# HPF_1_0.net
KiCad netlist of a schematic drawn in EAGLE
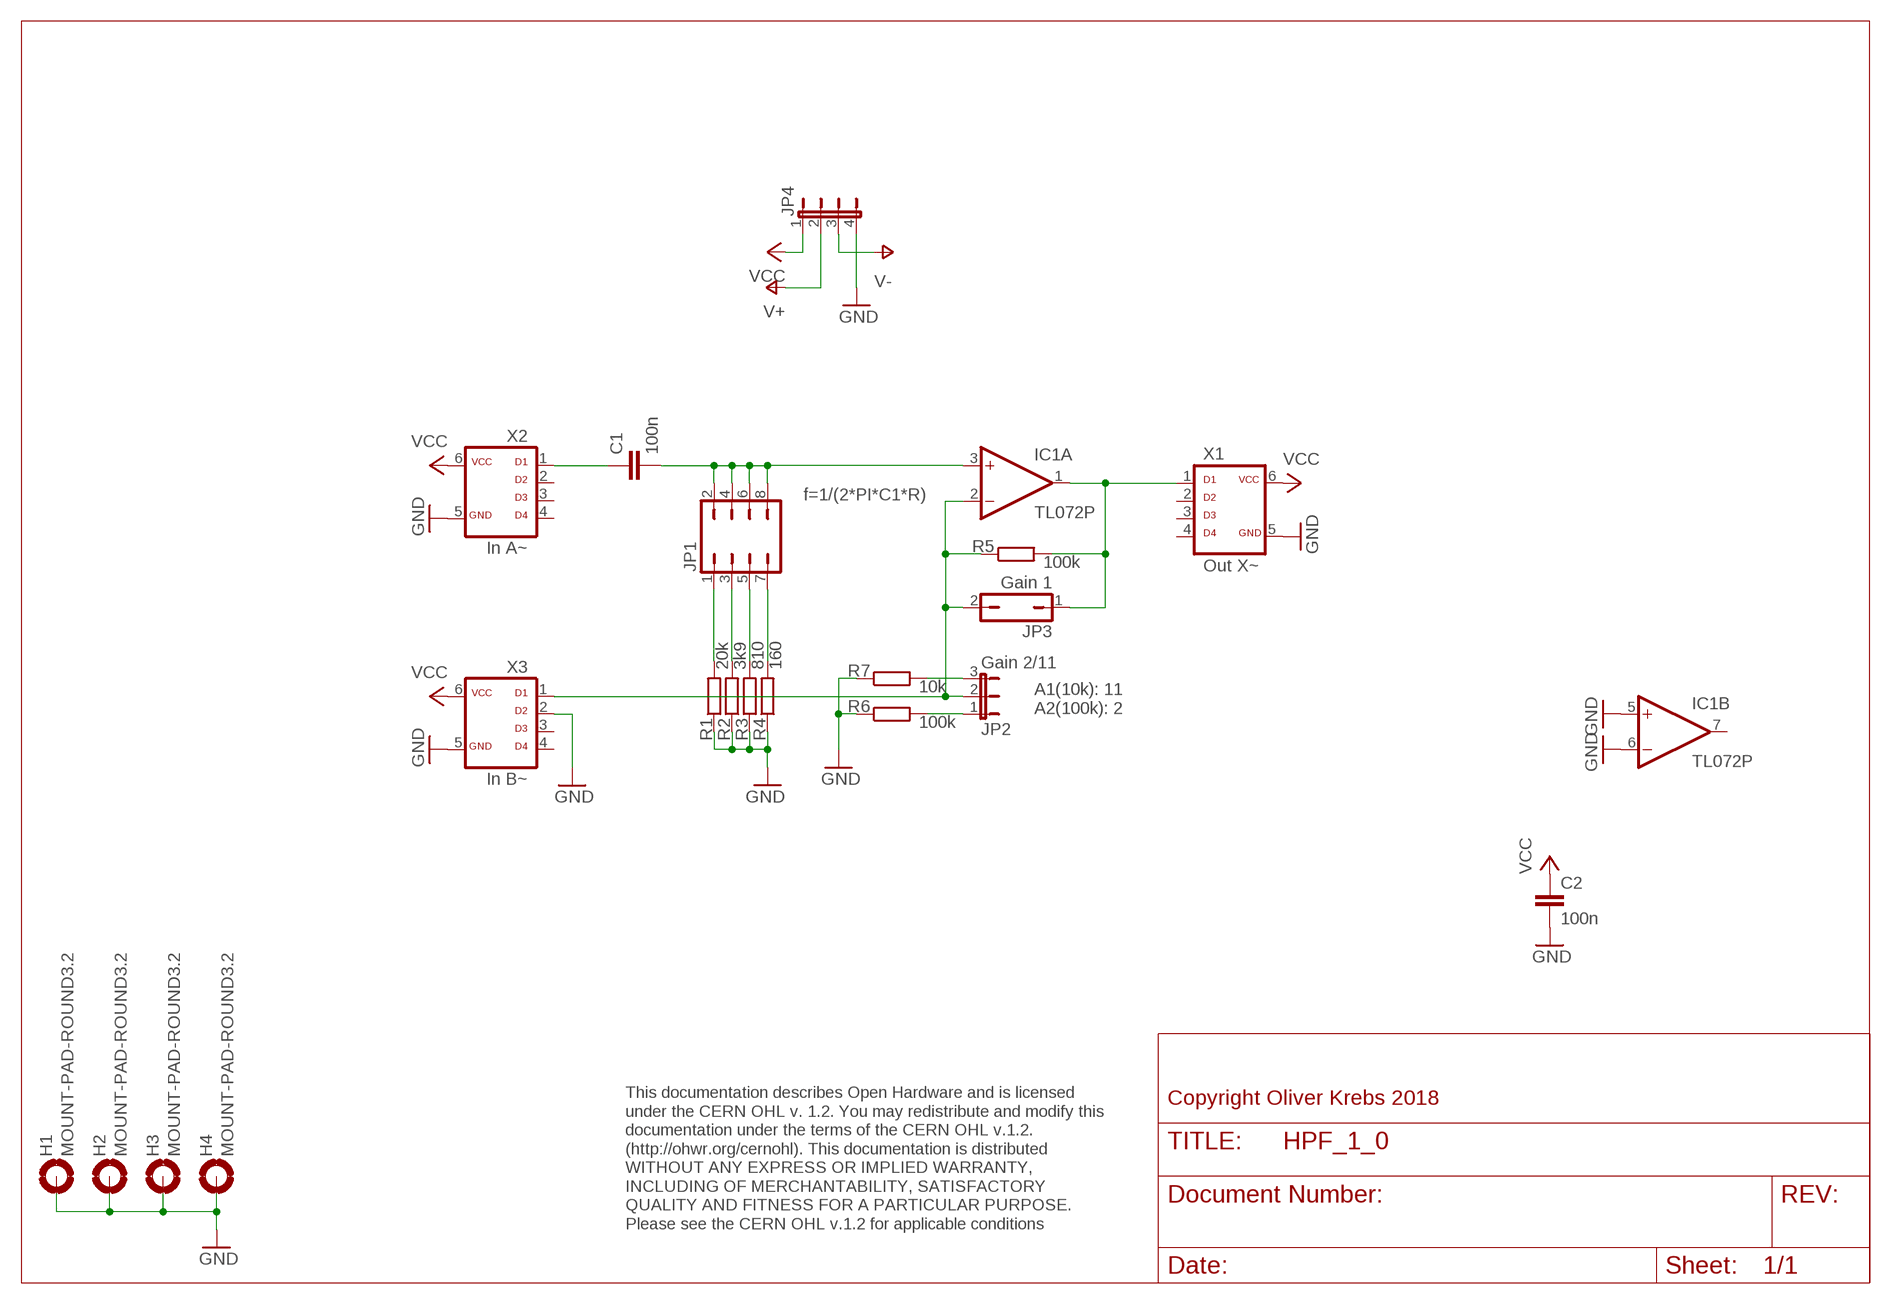
[diagram p0: schematic, sheet 1]

(export (version "E")
  (design (tool "Eeschema 10.0.6"))
  (components
    (comp (ref "C1")
      (value "100n")
      (footprint "eagle-import:C050-025X075")
      (libsource (lib "eagle-import") (part "C-EU050-025X075"))
    )
    (comp (ref "C2")
      (value "100n")
      (footprint "eagle-import:C050-025X075")
      (libsource (lib "eagle-import") (part "C-EU050-025X075"))
    )
    (comp (ref "H1")
      (value "MOUNT-PAD-ROUND3.2")
      (footprint "eagle-import:3,2-PAD")
      (libsource (lib "eagle-import") (part "MOUNT-PAD-ROUND3.2"))
    )
    (comp (ref "H2")
      (value "MOUNT-PAD-ROUND3.2")
      (footprint "eagle-import:3,2-PAD")
      (libsource (lib "eagle-import") (part "MOUNT-PAD-ROUND3.2"))
    )
    (comp (ref "H3")
      (value "MOUNT-PAD-ROUND3.2")
      (footprint "eagle-import:3,2-PAD")
      (libsource (lib "eagle-import") (part "MOUNT-PAD-ROUND3.2"))
    )
    (comp (ref "H4")
      (value "MOUNT-PAD-ROUND3.2")
      (footprint "eagle-import:3,2-PAD")
      (libsource (lib "eagle-import") (part "MOUNT-PAD-ROUND3.2"))
    )
    (comp (ref "IC1")
      (value "TL072P")
      (footprint "eagle-import:DIL08")
      (libsource (lib "eagle-import") (part "TL072P"))
    )
    (comp (ref "JP1")
      (value "JP4Q")
      (footprint "eagle-import:JP4Q")
      (libsource (lib "eagle-import") (part "JP4Q"))
    )
    (comp (ref "JP2")
      (value "Gain 2/11")
      (footprint "eagle-import:JP2-U")
      (libsource (lib "eagle-import") (part "JP2EJP2-U"))
    )
    (comp (ref "JP3")
      (value "Gain 1")
      (footprint "eagle-import:JP1")
      (libsource (lib "eagle-import") (part "JP1Q"))
    )
    (comp (ref "JP4")
      (value "JP4E")
      (footprint "eagle-import:JP4")
      (libsource (lib "eagle-import") (part "JP4E"))
    )
    (comp (ref "R1")
      (value "20k")
      (footprint "eagle-import:0207_10")
      (libsource (lib "eagle-import") (part "R-EU_0207/10"))
    )
    (comp (ref "R2")
      (value "3k9")
      (footprint "eagle-import:0207_10")
      (libsource (lib "eagle-import") (part "R-EU_0207/10"))
    )
    (comp (ref "R3")
      (value "810")
      (footprint "eagle-import:0207_10")
      (libsource (lib "eagle-import") (part "R-EU_0207/10"))
    )
    (comp (ref "R4")
      (value "160")
      (footprint "eagle-import:0207_10")
      (libsource (lib "eagle-import") (part "R-EU_0207/10"))
    )
    (comp (ref "R5")
      (value "100k")
      (footprint "eagle-import:0207_10")
      (libsource (lib "eagle-import") (part "R-EU_0207/10"))
    )
    (comp (ref "R6")
      (value "100k")
      (footprint "eagle-import:0207_10")
      (libsource (lib "eagle-import") (part "R-EU_0207/10"))
    )
    (comp (ref "R7")
      (value "10k")
      (footprint "eagle-import:0207_10")
      (libsource (lib "eagle-import") (part "R-EU_0207/10"))
    )
    (comp (ref "X1")
      (value "Out X~")
      (footprint "eagle-import:ML-6")
      (libsource (lib "eagle-import") (part "ML6D"))
    )
    (comp (ref "X2")
      (value "In A~")
      (footprint "eagle-import:ML-6")
      (libsource (lib "eagle-import") (part "ML6D"))
    )
    (comp (ref "X3")
      (value "In B~")
      (footprint "eagle-import:ML-6")
      (libsource (lib "eagle-import") (part "ML6D"))
    )
  )
  (nets
    (net (code "1") (name "GND") (class "Default")
      (node (ref "C2") (pin "2") (pinfunction "2_2") (pintype "passive"))
      (node (ref "H1") (pin "B3,2") (pinfunction "MOUNT_B3,2") (pintype "passive"))
      (node (ref "H2") (pin "B3,2") (pinfunction "MOUNT_B3,2") (pintype "passive"))
      (node (ref "H3") (pin "B3,2") (pinfunction "MOUNT_B3,2") (pintype "passive"))
      (node (ref "H4") (pin "B3,2") (pinfunction "MOUNT_B3,2") (pintype "passive"))
      (node (ref "IC1") (pin "5") (pinfunction "+IN_5") (pintype "input"))
      (node (ref "IC1") (pin "6") (pinfunction "-IN_6") (pintype "input"))
      (node (ref "JP4") (pin "4") (pinfunction "4_4") (pintype "passive"))
      (node (ref "R1") (pin "1") (pinfunction "1_1") (pintype "passive"))
      (node (ref "R2") (pin "1") (pinfunction "1_1") (pintype "passive"))
      (node (ref "R3") (pin "1") (pinfunction "1_1") (pintype "passive"))
      (node (ref "R4") (pin "1") (pinfunction "1_1") (pintype "passive"))
      (node (ref "R6") (pin "1") (pinfunction "1_1") (pintype "passive"))
      (node (ref "R7") (pin "1") (pinfunction "1_1") (pintype "passive"))
      (node (ref "X1") (pin "5") (pinfunction "5_5") (pintype "passive"))
      (node (ref "X2") (pin "5") (pinfunction "5_5") (pintype "passive"))
      (node (ref "X3") (pin "2") (pinfunction "2_2") (pintype "passive"))
      (node (ref "X3") (pin "5") (pinfunction "5_5") (pintype "passive"))
    )
    (net (code "2") (name "Net-(C1-Pad1)") (class "Default")
      (node (ref "C1") (pin "1") (pinfunction "1_1") (pintype "passive"))
      (node (ref "X2") (pin "1") (pinfunction "1_1") (pintype "passive"))
    )
    (net (code "3") (name "Net-(IC1A-+IN)") (class "Default")
      (node (ref "C1") (pin "2") (pinfunction "2_2") (pintype "passive"))
      (node (ref "IC1") (pin "3") (pinfunction "+IN_3") (pintype "input"))
      (node (ref "JP1") (pin "2") (pinfunction "2_2") (pintype "passive"))
      (node (ref "JP1") (pin "4") (pinfunction "4_4") (pintype "passive"))
      (node (ref "JP1") (pin "6") (pinfunction "6_6") (pintype "passive"))
      (node (ref "JP1") (pin "8") (pinfunction "8_8") (pintype "passive"))
    )
    (net (code "4") (name "Net-(IC1A--IN)") (class "Default")
      (node (ref "IC1") (pin "2") (pinfunction "-IN_2") (pintype "input"))
      (node (ref "JP2") (pin "2") (pinfunction "2_2") (pintype "passive"))
      (node (ref "JP3") (pin "2") (pinfunction "2_2") (pintype "passive"))
      (node (ref "R5") (pin "1") (pinfunction "1_1") (pintype "passive"))
      (node (ref "X3") (pin "1") (pinfunction "1_1") (pintype "passive"))
    )
    (net (code "5") (name "Net-(IC1A-OUT)") (class "Default")
      (node (ref "IC1") (pin "1") (pinfunction "OUT_1") (pintype "output"))
      (node (ref "JP3") (pin "1") (pinfunction "1_1") (pintype "passive"))
      (node (ref "R5") (pin "2") (pinfunction "2_2") (pintype "passive"))
      (node (ref "X1") (pin "1") (pinfunction "1_1") (pintype "passive"))
    )
    (net (code "6") (name "Net-(JP1-Pad1)") (class "Default")
      (node (ref "JP1") (pin "1") (pinfunction "1_1") (pintype "passive"))
      (node (ref "R1") (pin "2") (pinfunction "2_2") (pintype "passive"))
    )
    (net (code "7") (name "Net-(JP1-Pad3)") (class "Default")
      (node (ref "JP1") (pin "3") (pinfunction "3_3") (pintype "passive"))
      (node (ref "R2") (pin "2") (pinfunction "2_2") (pintype "passive"))
    )
    (net (code "8") (name "Net-(JP1-Pad5)") (class "Default")
      (node (ref "JP1") (pin "5") (pinfunction "5_5") (pintype "passive"))
      (node (ref "R3") (pin "2") (pinfunction "2_2") (pintype "passive"))
    )
    (net (code "9") (name "Net-(JP1-Pad7)") (class "Default")
      (node (ref "JP1") (pin "7") (pinfunction "7_7") (pintype "passive"))
      (node (ref "R4") (pin "2") (pinfunction "2_2") (pintype "passive"))
    )
    (net (code "10") (name "Net-(JP2-Pad1)") (class "Default")
      (node (ref "JP2") (pin "1") (pinfunction "1_1") (pintype "passive"))
      (node (ref "R6") (pin "2") (pinfunction "2_2") (pintype "passive"))
    )
    (net (code "11") (name "Net-(JP2-Pad3)") (class "Default")
      (node (ref "JP2") (pin "3") (pinfunction "3_3") (pintype "passive"))
      (node (ref "R7") (pin "2") (pinfunction "2_2") (pintype "passive"))
    )
    (net (code "12") (name "V+") (class "Default")
      (node (ref "JP4") (pin "2") (pinfunction "2_2") (pintype "passive"))
    )
    (net (code "13") (name "V-") (class "Default")
      (node (ref "JP4") (pin "3") (pinfunction "3_3") (pintype "passive"))
    )
    (net (code "14") (name "VCC") (class "Default")
      (node (ref "C2") (pin "1") (pinfunction "1_1") (pintype "passive"))
      (node (ref "JP4") (pin "1") (pinfunction "1_1") (pintype "passive"))
      (node (ref "X1") (pin "6") (pinfunction "6_6") (pintype "passive"))
      (node (ref "X2") (pin "6") (pinfunction "6_6") (pintype "passive"))
      (node (ref "X3") (pin "6") (pinfunction "6_6") (pintype "passive"))
    )
    (net (code "15") (name "unconnected-(IC1B-OUT-Pad7)") (class "Default")
      (node (ref "IC1") (pin "7") (pinfunction "OUT_7") (pintype "output"))
    )
    (net (code "16") (name "unconnected-(X1-Pad2)") (class "Default")
      (node (ref "X1") (pin "2") (pinfunction "2_2") (pintype "passive"))
    )
    (net (code "17") (name "unconnected-(X1-Pad3)") (class "Default")
      (node (ref "X1") (pin "3") (pinfunction "3_3") (pintype "passive"))
    )
    (net (code "18") (name "unconnected-(X1-Pad4)") (class "Default")
      (node (ref "X1") (pin "4") (pinfunction "4_4") (pintype "passive"))
    )
    (net (code "19") (name "unconnected-(X2-Pad2)") (class "Default")
      (node (ref "X2") (pin "2") (pinfunction "2_2") (pintype "passive"))
    )
    (net (code "20") (name "unconnected-(X2-Pad3)") (class "Default")
      (node (ref "X2") (pin "3") (pinfunction "3_3") (pintype "passive"))
    )
    (net (code "21") (name "unconnected-(X2-Pad4)") (class "Default")
      (node (ref "X2") (pin "4") (pinfunction "4_4") (pintype "passive"))
    )
    (net (code "22") (name "unconnected-(X3-Pad3)") (class "Default")
      (node (ref "X3") (pin "3") (pinfunction "3_3") (pintype "passive"))
    )
    (net (code "23") (name "unconnected-(X3-Pad4)") (class "Default")
      (node (ref "X3") (pin "4") (pinfunction "4_4") (pintype "passive"))
    )
  )
)
